# mofang.net
KiCad netlist of a schematic drawn in Altium Designer
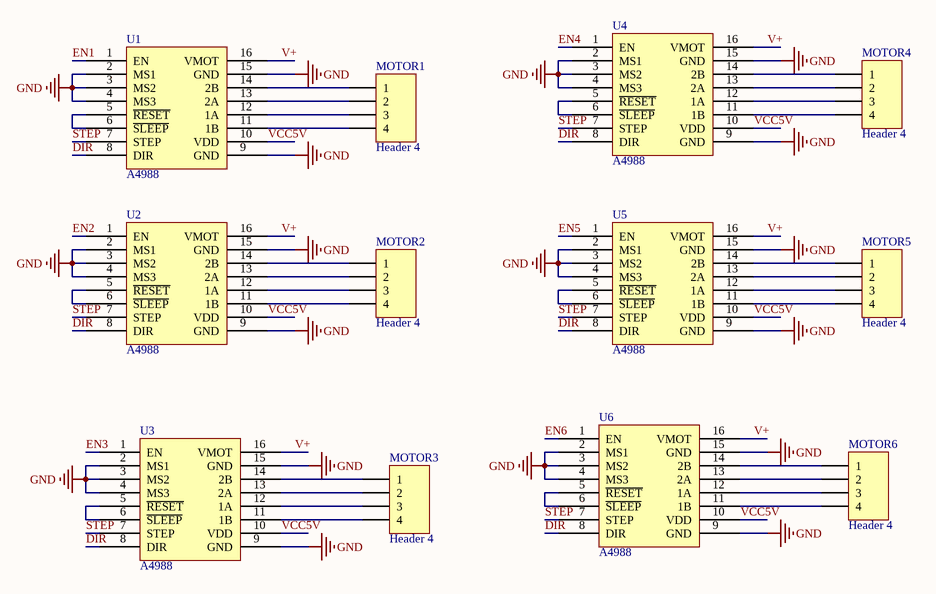
[diagram p0: mofang.SchDoc]

(export (version "E")
  (design (tool "Eeschema 10.0.6"))
  (components
    (comp (ref "MOTOR1")
      (value "Header 4")
      (footprint "HDR1X4")
      (description "Header, 4-Pin")
      (fields (field (name "PUBLISHER") "Altium Limited"))
      (libsource (lib "Miscellaneous Connectors") (part "Header 4"))
    )
    (comp (ref "MOTOR2")
      (value "Header 4")
      (footprint "HDR1X4")
      (description "Header, 4-Pin")
      (fields (field (name "PUBLISHER") "Altium Limited"))
      (libsource (lib "Miscellaneous Connectors") (part "Header 4"))
    )
    (comp (ref "MOTOR3")
      (value "Header 4")
      (footprint "HDR1X4")
      (description "Header, 4-Pin")
      (fields (field (name "PUBLISHER") "Altium Limited"))
      (libsource (lib "Miscellaneous Connectors") (part "Header 4"))
    )
    (comp (ref "MOTOR4")
      (value "Header 4")
      (footprint "HDR1X4")
      (description "Header, 4-Pin")
      (fields (field (name "PUBLISHER") "Altium Limited"))
      (libsource (lib "Miscellaneous Connectors") (part "Header 4"))
    )
    (comp (ref "MOTOR5")
      (value "Header 4")
      (footprint "HDR1X4")
      (description "Header, 4-Pin")
      (fields (field (name "PUBLISHER") "Altium Limited"))
      (libsource (lib "Miscellaneous Connectors") (part "Header 4"))
    )
    (comp (ref "MOTOR6")
      (value "Header 4")
      (footprint "HDR1X4")
      (description "Header, 4-Pin")
      (fields (field (name "PUBLISHER") "Altium Limited"))
      (libsource (lib "Miscellaneous Connectors") (part "Header 4"))
    )
    (comp (ref "U1") (value "A4988") (footprint "A4988") (libsource (lib "Schlib1") (part "A4988")))
    (comp (ref "U2") (value "A4988") (footprint "A4988") (libsource (lib "Schlib1") (part "A4988")))
    (comp (ref "U3") (value "A4988") (footprint "A4988") (libsource (lib "Schlib1") (part "A4988")))
    (comp (ref "U4") (value "A4988") (footprint "A4988") (libsource (lib "Schlib1") (part "A4988")))
    (comp (ref "U5") (value "A4988") (footprint "A4988") (libsource (lib "Schlib1") (part "A4988")))
    (comp (ref "U6") (value "A4988") (footprint "A4988") (libsource (lib "Schlib1") (part "A4988")))
  )
  (nets
    (net (code "1") (name "/DIR") (class "Default")
      (node (ref "U1") (pin "8") (pinfunction "DIR_8") (pintype "passive"))
      (node (ref "U2") (pin "8") (pinfunction "DIR_8") (pintype "passive"))
      (node (ref "U3") (pin "8") (pinfunction "DIR_8") (pintype "passive"))
      (node (ref "U4") (pin "8") (pinfunction "DIR_8") (pintype "passive"))
      (node (ref "U5") (pin "8") (pinfunction "DIR_8") (pintype "passive"))
      (node (ref "U6") (pin "8") (pinfunction "DIR_8") (pintype "passive"))
    )
    (net (code "2") (name "/EN1") (class "Default")
      (node (ref "U1") (pin "1") (pinfunction "EN_1") (pintype "passive"))
    )
    (net (code "3") (name "/EN2") (class "Default")
      (node (ref "U2") (pin "1") (pinfunction "EN_1") (pintype "passive"))
    )
    (net (code "4") (name "/EN3") (class "Default")
      (node (ref "U3") (pin "1") (pinfunction "EN_1") (pintype "passive"))
    )
    (net (code "5") (name "/EN4") (class "Default")
      (node (ref "U4") (pin "1") (pinfunction "EN_1") (pintype "passive"))
    )
    (net (code "6") (name "/EN5") (class "Default")
      (node (ref "U5") (pin "1") (pinfunction "EN_1") (pintype "passive"))
    )
    (net (code "7") (name "/EN6") (class "Default")
      (node (ref "U6") (pin "1") (pinfunction "EN_1") (pintype "passive"))
    )
    (net (code "8") (name "/STEP") (class "Default")
      (node (ref "U1") (pin "7") (pinfunction "STEP_7") (pintype "passive"))
      (node (ref "U2") (pin "7") (pinfunction "STEP_7") (pintype "passive"))
      (node (ref "U3") (pin "7") (pinfunction "STEP_7") (pintype "passive"))
      (node (ref "U4") (pin "7") (pinfunction "STEP_7") (pintype "passive"))
      (node (ref "U5") (pin "7") (pinfunction "STEP_7") (pintype "passive"))
      (node (ref "U6") (pin "7") (pinfunction "STEP_7") (pintype "passive"))
    )
    (net (code "9") (name "/V+") (class "Default")
      (node (ref "U1") (pin "16") (pinfunction "VMOT_16") (pintype "passive"))
      (node (ref "U2") (pin "16") (pinfunction "VMOT_16") (pintype "passive"))
      (node (ref "U3") (pin "16") (pinfunction "VMOT_16") (pintype "passive"))
      (node (ref "U4") (pin "16") (pinfunction "VMOT_16") (pintype "passive"))
      (node (ref "U5") (pin "16") (pinfunction "VMOT_16") (pintype "passive"))
      (node (ref "U6") (pin "16") (pinfunction "VMOT_16") (pintype "passive"))
    )
    (net (code "10") (name "/VCC5V") (class "Default")
      (node (ref "U1") (pin "10") (pinfunction "VDD_10") (pintype "passive"))
      (node (ref "U2") (pin "10") (pinfunction "VDD_10") (pintype "passive"))
      (node (ref "U3") (pin "10") (pinfunction "VDD_10") (pintype "passive"))
      (node (ref "U4") (pin "10") (pinfunction "VDD_10") (pintype "passive"))
      (node (ref "U5") (pin "10") (pinfunction "VDD_10") (pintype "passive"))
      (node (ref "U6") (pin "10") (pinfunction "VDD_10") (pintype "passive"))
    )
    (net (code "11") (name "GND") (class "Default")
      (node (ref "U1") (pin "15") (pinfunction "GND_15") (pintype "passive"))
      (node (ref "U1") (pin "2") (pinfunction "MS1_2") (pintype "passive"))
      (node (ref "U1") (pin "3") (pinfunction "MS2_3") (pintype "passive"))
      (node (ref "U1") (pin "4") (pinfunction "MS3_4") (pintype "passive"))
      (node (ref "U1") (pin "9") (pinfunction "GND_9") (pintype "passive"))
      (node (ref "U2") (pin "15") (pinfunction "GND_15") (pintype "passive"))
      (node (ref "U2") (pin "2") (pinfunction "MS1_2") (pintype "passive"))
      (node (ref "U2") (pin "3") (pinfunction "MS2_3") (pintype "passive"))
      (node (ref "U2") (pin "4") (pinfunction "MS3_4") (pintype "passive"))
      (node (ref "U2") (pin "9") (pinfunction "GND_9") (pintype "passive"))
      (node (ref "U3") (pin "15") (pinfunction "GND_15") (pintype "passive"))
      (node (ref "U3") (pin "2") (pinfunction "MS1_2") (pintype "passive"))
      (node (ref "U3") (pin "3") (pinfunction "MS2_3") (pintype "passive"))
      (node (ref "U3") (pin "4") (pinfunction "MS3_4") (pintype "passive"))
      (node (ref "U3") (pin "9") (pinfunction "GND_9") (pintype "passive"))
      (node (ref "U4") (pin "15") (pinfunction "GND_15") (pintype "passive"))
      (node (ref "U4") (pin "2") (pinfunction "MS1_2") (pintype "passive"))
      (node (ref "U4") (pin "3") (pinfunction "MS2_3") (pintype "passive"))
      (node (ref "U4") (pin "4") (pinfunction "MS3_4") (pintype "passive"))
      (node (ref "U4") (pin "9") (pinfunction "GND_9") (pintype "passive"))
      (node (ref "U5") (pin "15") (pinfunction "GND_15") (pintype "passive"))
      (node (ref "U5") (pin "2") (pinfunction "MS1_2") (pintype "passive"))
      (node (ref "U5") (pin "3") (pinfunction "MS2_3") (pintype "passive"))
      (node (ref "U5") (pin "4") (pinfunction "MS3_4") (pintype "passive"))
      (node (ref "U5") (pin "9") (pinfunction "GND_9") (pintype "passive"))
      (node (ref "U6") (pin "15") (pinfunction "GND_15") (pintype "passive"))
      (node (ref "U6") (pin "2") (pinfunction "MS1_2") (pintype "passive"))
      (node (ref "U6") (pin "3") (pinfunction "MS2_3") (pintype "passive"))
      (node (ref "U6") (pin "4") (pinfunction "MS3_4") (pintype "passive"))
      (node (ref "U6") (pin "9") (pinfunction "GND_9") (pintype "passive"))
    )
    (net (code "12") (name "Net-(U1-1A)") (class "Default")
      (node (ref "MOTOR1") (pin "3") (pinfunction "3_3") (pintype "passive"))
      (node (ref "U1") (pin "12") (pinfunction "1A_12") (pintype "passive"))
    )
    (net (code "13") (name "Net-(U1-1B)") (class "Default")
      (node (ref "MOTOR1") (pin "4") (pinfunction "4_4") (pintype "passive"))
      (node (ref "U1") (pin "11") (pinfunction "1B_11") (pintype "passive"))
    )
    (net (code "14") (name "Net-(U1-2A)") (class "Default")
      (node (ref "MOTOR1") (pin "2") (pinfunction "2_2") (pintype "passive"))
      (node (ref "U1") (pin "13") (pinfunction "2A_13") (pintype "passive"))
    )
    (net (code "15") (name "Net-(U1-2B)") (class "Default")
      (node (ref "MOTOR1") (pin "1") (pinfunction "1_1") (pintype "passive"))
      (node (ref "U1") (pin "14") (pinfunction "2B_14") (pintype "passive"))
    )
    (net (code "16") (name "Net-(U1-~{RESET})") (class "Default")
      (node (ref "U1") (pin "5") (pinfunction "~{RESET}_5") (pintype "passive"))
      (node (ref "U1") (pin "6") (pinfunction "~{SLEEP}_6") (pintype "passive"))
    )
    (net (code "17") (name "Net-(U2-1A)") (class "Default")
      (node (ref "MOTOR2") (pin "3") (pinfunction "3_3") (pintype "passive"))
      (node (ref "U2") (pin "12") (pinfunction "1A_12") (pintype "passive"))
    )
    (net (code "18") (name "Net-(U2-1B)") (class "Default")
      (node (ref "MOTOR2") (pin "4") (pinfunction "4_4") (pintype "passive"))
      (node (ref "U2") (pin "11") (pinfunction "1B_11") (pintype "passive"))
    )
    (net (code "19") (name "Net-(U2-2A)") (class "Default")
      (node (ref "MOTOR2") (pin "2") (pinfunction "2_2") (pintype "passive"))
      (node (ref "U2") (pin "13") (pinfunction "2A_13") (pintype "passive"))
    )
    (net (code "20") (name "Net-(U2-2B)") (class "Default")
      (node (ref "MOTOR2") (pin "1") (pinfunction "1_1") (pintype "passive"))
      (node (ref "U2") (pin "14") (pinfunction "2B_14") (pintype "passive"))
    )
    (net (code "21") (name "Net-(U2-~{RESET})") (class "Default")
      (node (ref "U2") (pin "5") (pinfunction "~{RESET}_5") (pintype "passive"))
      (node (ref "U2") (pin "6") (pinfunction "~{SLEEP}_6") (pintype "passive"))
    )
    (net (code "22") (name "Net-(U3-1A)") (class "Default")
      (node (ref "MOTOR3") (pin "3") (pinfunction "3_3") (pintype "passive"))
      (node (ref "U3") (pin "12") (pinfunction "1A_12") (pintype "passive"))
    )
    (net (code "23") (name "Net-(U3-1B)") (class "Default")
      (node (ref "MOTOR3") (pin "4") (pinfunction "4_4") (pintype "passive"))
      (node (ref "U3") (pin "11") (pinfunction "1B_11") (pintype "passive"))
    )
    (net (code "24") (name "Net-(U3-2A)") (class "Default")
      (node (ref "MOTOR3") (pin "2") (pinfunction "2_2") (pintype "passive"))
      (node (ref "U3") (pin "13") (pinfunction "2A_13") (pintype "passive"))
    )
    (net (code "25") (name "Net-(U3-2B)") (class "Default")
      (node (ref "MOTOR3") (pin "1") (pinfunction "1_1") (pintype "passive"))
      (node (ref "U3") (pin "14") (pinfunction "2B_14") (pintype "passive"))
    )
    (net (code "26") (name "Net-(U3-~{RESET})") (class "Default")
      (node (ref "U3") (pin "5") (pinfunction "~{RESET}_5") (pintype "passive"))
      (node (ref "U3") (pin "6") (pinfunction "~{SLEEP}_6") (pintype "passive"))
    )
    (net (code "27") (name "Net-(U4-1A)") (class "Default")
      (node (ref "MOTOR4") (pin "3") (pinfunction "3_3") (pintype "passive"))
      (node (ref "U4") (pin "12") (pinfunction "1A_12") (pintype "passive"))
    )
    (net (code "28") (name "Net-(U4-1B)") (class "Default")
      (node (ref "MOTOR4") (pin "4") (pinfunction "4_4") (pintype "passive"))
      (node (ref "U4") (pin "11") (pinfunction "1B_11") (pintype "passive"))
    )
    (net (code "29") (name "Net-(U4-2A)") (class "Default")
      (node (ref "MOTOR4") (pin "2") (pinfunction "2_2") (pintype "passive"))
      (node (ref "U4") (pin "13") (pinfunction "2A_13") (pintype "passive"))
    )
    (net (code "30") (name "Net-(U4-2B)") (class "Default")
      (node (ref "MOTOR4") (pin "1") (pinfunction "1_1") (pintype "passive"))
      (node (ref "U4") (pin "14") (pinfunction "2B_14") (pintype "passive"))
    )
    (net (code "31") (name "Net-(U4-~{RESET})") (class "Default")
      (node (ref "U4") (pin "5") (pinfunction "~{RESET}_5") (pintype "passive"))
      (node (ref "U4") (pin "6") (pinfunction "~{SLEEP}_6") (pintype "passive"))
    )
    (net (code "32") (name "Net-(U5-1A)") (class "Default")
      (node (ref "MOTOR5") (pin "3") (pinfunction "3_3") (pintype "passive"))
      (node (ref "U5") (pin "12") (pinfunction "1A_12") (pintype "passive"))
    )
    (net (code "33") (name "Net-(U5-1B)") (class "Default")
      (node (ref "MOTOR5") (pin "4") (pinfunction "4_4") (pintype "passive"))
      (node (ref "U5") (pin "11") (pinfunction "1B_11") (pintype "passive"))
    )
    (net (code "34") (name "Net-(U5-2A)") (class "Default")
      (node (ref "MOTOR5") (pin "2") (pinfunction "2_2") (pintype "passive"))
      (node (ref "U5") (pin "13") (pinfunction "2A_13") (pintype "passive"))
    )
    (net (code "35") (name "Net-(U5-2B)") (class "Default")
      (node (ref "MOTOR5") (pin "1") (pinfunction "1_1") (pintype "passive"))
      (node (ref "U5") (pin "14") (pinfunction "2B_14") (pintype "passive"))
    )
    (net (code "36") (name "Net-(U5-~{RESET})") (class "Default")
      (node (ref "U5") (pin "5") (pinfunction "~{RESET}_5") (pintype "passive"))
      (node (ref "U5") (pin "6") (pinfunction "~{SLEEP}_6") (pintype "passive"))
    )
    (net (code "37") (name "Net-(U6-1A)") (class "Default")
      (node (ref "MOTOR6") (pin "3") (pinfunction "3_3") (pintype "passive"))
      (node (ref "U6") (pin "12") (pinfunction "1A_12") (pintype "passive"))
    )
    (net (code "38") (name "Net-(U6-1B)") (class "Default")
      (node (ref "MOTOR6") (pin "4") (pinfunction "4_4") (pintype "passive"))
      (node (ref "U6") (pin "11") (pinfunction "1B_11") (pintype "passive"))
    )
    (net (code "39") (name "Net-(U6-2A)") (class "Default")
      (node (ref "MOTOR6") (pin "2") (pinfunction "2_2") (pintype "passive"))
      (node (ref "U6") (pin "13") (pinfunction "2A_13") (pintype "passive"))
    )
    (net (code "40") (name "Net-(U6-2B)") (class "Default")
      (node (ref "MOTOR6") (pin "1") (pinfunction "1_1") (pintype "passive"))
      (node (ref "U6") (pin "14") (pinfunction "2B_14") (pintype "passive"))
    )
    (net (code "41") (name "Net-(U6-~{RESET})") (class "Default")
      (node (ref "U6") (pin "5") (pinfunction "~{RESET}_5") (pintype "passive"))
      (node (ref "U6") (pin "6") (pinfunction "~{SLEEP}_6") (pintype "passive"))
    )
  )
)
